# uMultimeter_Exp_Sch.net
KiCad netlist of a schematic drawn in Altium Designer
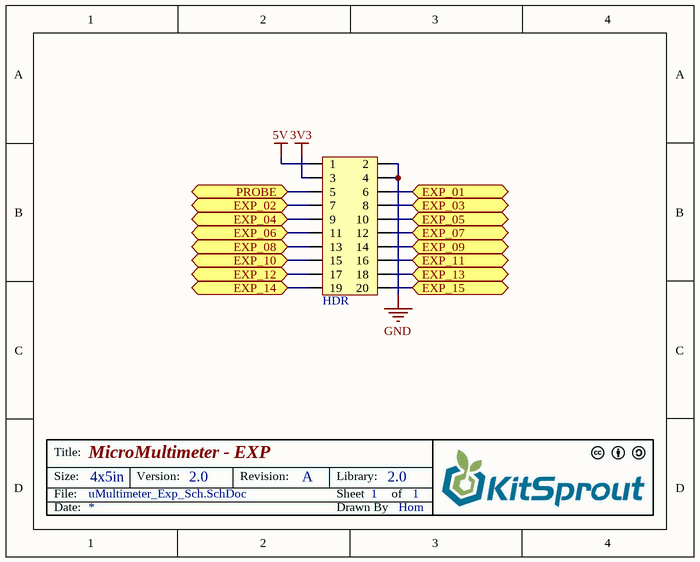
[diagram p0: uMultimeter_Exp_Sch.SchDoc]

(export (version "E")
  (design (tool "Eeschema 10.0.6"))
  (components
    (comp (ref "HDR")
      (value "HDR2x10_2.54")
      (footprint "PCB_ConnectorHDR:HDR2X10_2.54_180H")
      (description "Header")
      (libsource (lib "SCH_ConnectorHDR") (part "HDR2x10_2.54"))
    )
  )
  (nets
    (net (code "1") (name "/EXP_01") (class "Default")
      (node (ref "HDR") (pin "6") (pinfunction "6_6") (pintype "passive"))
    )
    (net (code "2") (name "/EXP_02") (class "Default")
      (node (ref "HDR") (pin "7") (pinfunction "7_7") (pintype "passive"))
    )
    (net (code "3") (name "/EXP_03") (class "Default")
      (node (ref "HDR") (pin "8") (pinfunction "8_8") (pintype "passive"))
    )
    (net (code "4") (name "/EXP_04") (class "Default")
      (node (ref "HDR") (pin "9") (pinfunction "9_9") (pintype "passive"))
    )
    (net (code "5") (name "/EXP_05") (class "Default")
      (node (ref "HDR") (pin "10") (pinfunction "10_10") (pintype "passive"))
    )
    (net (code "6") (name "/EXP_06") (class "Default")
      (node (ref "HDR") (pin "11") (pinfunction "11_11") (pintype "passive"))
    )
    (net (code "7") (name "/EXP_07") (class "Default")
      (node (ref "HDR") (pin "12") (pinfunction "12_12") (pintype "passive"))
    )
    (net (code "8") (name "/EXP_08") (class "Default")
      (node (ref "HDR") (pin "13") (pinfunction "13_13") (pintype "passive"))
    )
    (net (code "9") (name "/EXP_09") (class "Default")
      (node (ref "HDR") (pin "14") (pinfunction "14_14") (pintype "passive"))
    )
    (net (code "10") (name "/EXP_10") (class "Default")
      (node (ref "HDR") (pin "15") (pinfunction "15_15") (pintype "passive"))
    )
    (net (code "11") (name "/EXP_11") (class "Default")
      (node (ref "HDR") (pin "16") (pinfunction "16_16") (pintype "passive"))
    )
    (net (code "12") (name "/EXP_12") (class "Default")
      (node (ref "HDR") (pin "17") (pinfunction "17_17") (pintype "passive"))
    )
    (net (code "13") (name "/EXP_13") (class "Default")
      (node (ref "HDR") (pin "18") (pinfunction "18_18") (pintype "passive"))
    )
    (net (code "14") (name "/EXP_14") (class "Default")
      (node (ref "HDR") (pin "19") (pinfunction "19_19") (pintype "passive"))
    )
    (net (code "15") (name "/EXP_15") (class "Default")
      (node (ref "HDR") (pin "20") (pinfunction "20_20") (pintype "passive"))
    )
    (net (code "16") (name "/PROBE") (class "Default")
      (node (ref "HDR") (pin "5") (pinfunction "5_5") (pintype "passive"))
    )
    (net (code "17") (name "3V3") (class "Default")
      (node (ref "HDR") (pin "3") (pinfunction "3_3") (pintype "passive"))
    )
    (net (code "18") (name "5V") (class "Default")
      (node (ref "HDR") (pin "1") (pinfunction "1_1") (pintype "passive"))
    )
    (net (code "19") (name "GND") (class "Default")
      (node (ref "HDR") (pin "2") (pinfunction "2_2") (pintype "passive"))
      (node (ref "HDR") (pin "4") (pinfunction "4_4") (pintype "passive"))
    )
  )
)
